# Harp_Motor_H2-module_v1_0.net
KiCad netlist of a schematic drawn in EAGLE
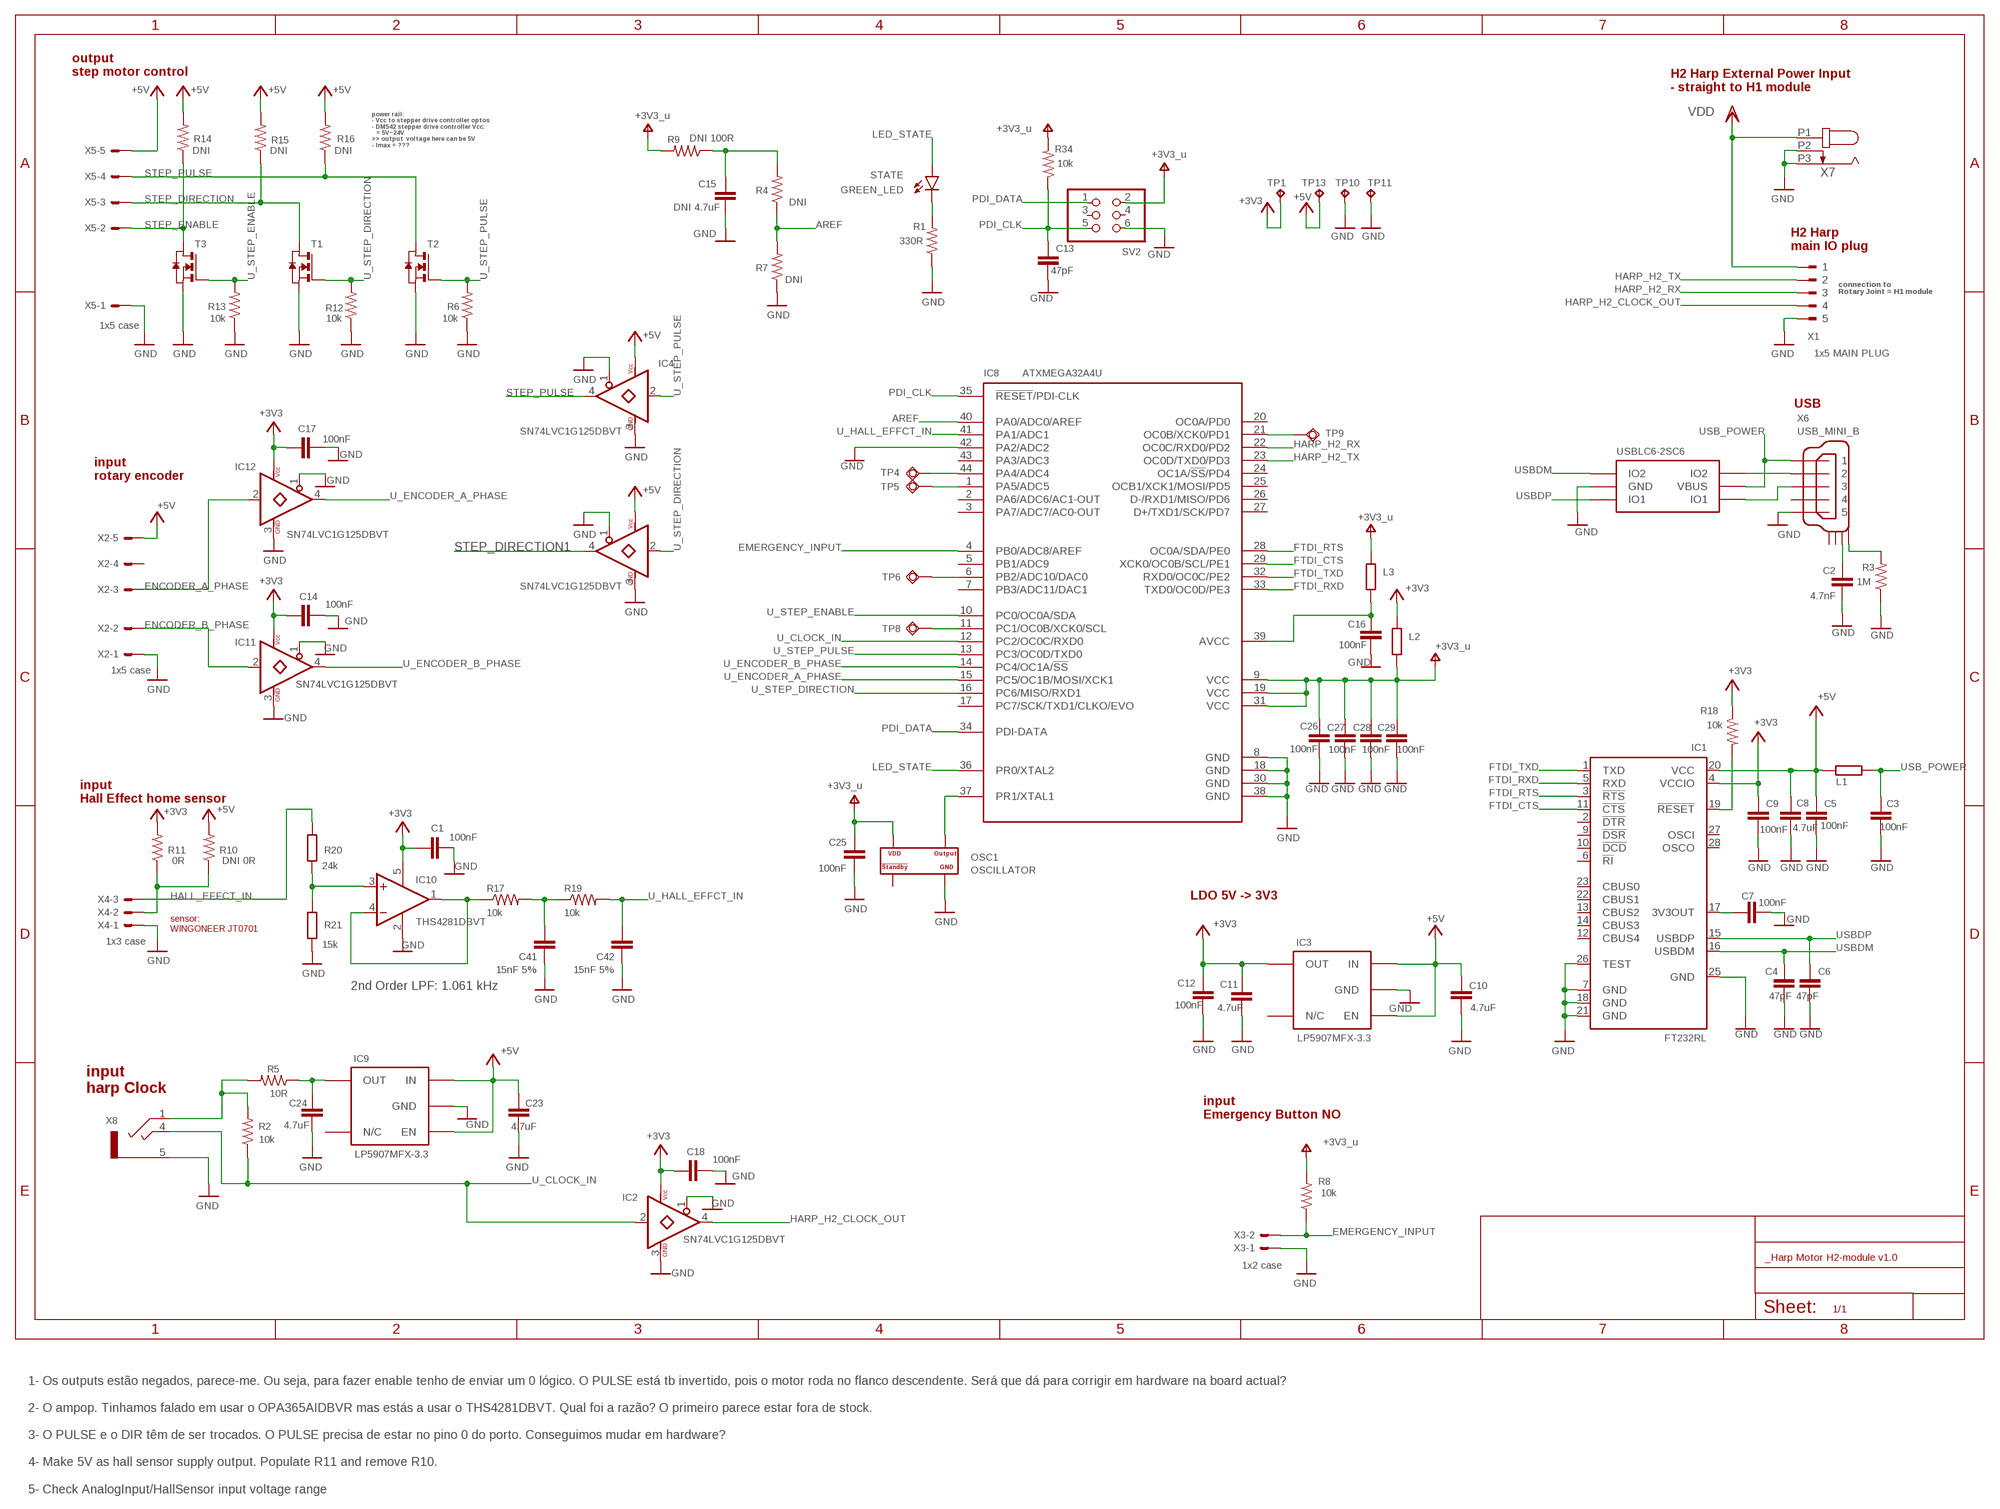
[diagram p0: schematic, sheet 1]

(export (version "E")
  (design (tool "Eeschema 10.0.6"))
  (components
    (comp (ref "C1")
      (value "100nF")
      (footprint "eagle-import:C0402K")
      (fields (field (name "MPN") "C1005X7R1H104K050BB"))
      (libsource (lib "eagle-import") (part "C-EUC0402K"))
    )
    (comp (ref "C2")
      (value "4.7nF")
      (footprint "eagle-import:C0402K")
      (fields (field (name "MPN") "CC0402KRX7R8BB472"))
      (libsource (lib "eagle-import") (part "C-EUC0402K"))
    )
    (comp (ref "C3")
      (value "100nF")
      (footprint "eagle-import:C0402K")
      (fields (field (name "MPN") "C1005X7R1H104K050BB"))
      (libsource (lib "eagle-import") (part "C-EUC0402K"))
    )
    (comp (ref "C4")
      (value "47pF")
      (footprint "eagle-import:C0402K")
      (fields (field (name "MPN") "04025A470JAT2A"))
      (libsource (lib "eagle-import") (part "C-EUC0402K"))
    )
    (comp (ref "C5")
      (value "100nF")
      (footprint "eagle-import:C0402K")
      (fields (field (name "MPN") "C1005X7R1H104K050BB"))
      (libsource (lib "eagle-import") (part "C-EUC0402K"))
    )
    (comp (ref "C6")
      (value "47pF")
      (footprint "eagle-import:C0402K")
      (fields (field (name "MPN") "04025A470JAT2A"))
      (libsource (lib "eagle-import") (part "C-EUC0402K"))
    )
    (comp (ref "C7")
      (value "100nF")
      (footprint "eagle-import:C0402K")
      (fields (field (name "MPN") "C1005X7R1H104K050BB"))
      (libsource (lib "eagle-import") (part "C-EUC0402K"))
    )
    (comp (ref "C8")
      (value "4.7uF")
      (footprint "eagle-import:C0603K")
      (fields (field (name "MPN") "C1608X6S1C475K080AC"))
      (libsource (lib "eagle-import") (part "C-EUC0603K"))
    )
    (comp (ref "C9")
      (value "100nF")
      (footprint "eagle-import:C0402K")
      (fields (field (name "MPN") "C1005X7R1H104K050BB"))
      (libsource (lib "eagle-import") (part "C-EUC0402K"))
    )
    (comp (ref "C10")
      (value "4.7uF")
      (footprint "eagle-import:C0603K")
      (fields (field (name "MPN") "C1608X6S1C475K080AC"))
      (libsource (lib "eagle-import") (part "C-EUC0603K"))
    )
    (comp (ref "C11")
      (value "4.7uF")
      (footprint "eagle-import:C0603K")
      (fields (field (name "MPN") "C1608X6S1C475K080AC"))
      (libsource (lib "eagle-import") (part "C-EUC0603K"))
    )
    (comp (ref "C12")
      (value "100nF")
      (footprint "eagle-import:C0402K")
      (fields (field (name "MPN") "C1005X7R1H104K050BB"))
      (libsource (lib "eagle-import") (part "C-EUC0402K"))
    )
    (comp (ref "C13")
      (value "47pF")
      (footprint "eagle-import:C0402K")
      (fields (field (name "MPN") "04025A470JAT2A"))
      (libsource (lib "eagle-import") (part "C-EUC0402K"))
    )
    (comp (ref "C14")
      (value "100nF")
      (footprint "eagle-import:C0402K")
      (fields (field (name "MPN") "C1005X7R1H104K050BB"))
      (libsource (lib "eagle-import") (part "C-EUC0402K"))
    )
    (comp (ref "C15")
      (value "DNI 4.7uF")
      (footprint "eagle-import:C0603K")
      (fields (field (name "MPN") "C1608X6S1C475K080AC"))
      (libsource (lib "eagle-import") (part "C-EUC0603K"))
    )
    (comp (ref "C16")
      (value "100nF")
      (footprint "eagle-import:C0402K")
      (fields (field (name "MPN") "C1005X7R1H104K050BB"))
      (libsource (lib "eagle-import") (part "C-EUC0402K"))
    )
    (comp (ref "C17")
      (value "100nF")
      (footprint "eagle-import:C0402K")
      (fields (field (name "MPN") "C1005X7R1H104K050BB"))
      (libsource (lib "eagle-import") (part "C-EUC0402K"))
    )
    (comp (ref "C18")
      (value "100nF")
      (footprint "eagle-import:C0402K")
      (fields (field (name "MPN") "C1005X7R1H104K050BB"))
      (libsource (lib "eagle-import") (part "C-EUC0402K"))
    )
    (comp (ref "C23")
      (value "4.7uF")
      (footprint "eagle-import:C0603K")
      (fields (field (name "MPN") "C1608X6S1C475K080AC"))
      (libsource (lib "eagle-import") (part "C-EUC0603K"))
    )
    (comp (ref "C24")
      (value "4.7uF")
      (footprint "eagle-import:C0603K")
      (fields (field (name "MPN") "C1608X6S1C475K080AC"))
      (libsource (lib "eagle-import") (part "C-EUC0603K"))
    )
    (comp (ref "C25")
      (value "100nF")
      (footprint "eagle-import:C0402K")
      (fields (field (name "MPN") "C1005X7R1H104K050BB"))
      (libsource (lib "eagle-import") (part "C-EUC0402K"))
    )
    (comp (ref "C26")
      (value "100nF")
      (footprint "eagle-import:C0402K")
      (fields (field (name "MPN") "C1005X7R1H104K050BB"))
      (libsource (lib "eagle-import") (part "C-EUC0402K"))
    )
    (comp (ref "C27")
      (value "100nF")
      (footprint "eagle-import:C0402K")
      (fields (field (name "MPN") "C1005X7R1H104K050BB"))
      (libsource (lib "eagle-import") (part "C-EUC0402K"))
    )
    (comp (ref "C28")
      (value "100nF")
      (footprint "eagle-import:C0402K")
      (fields (field (name "MPN") "C1005X7R1H104K050BB"))
      (libsource (lib "eagle-import") (part "C-EUC0402K"))
    )
    (comp (ref "C29")
      (value "100nF")
      (footprint "eagle-import:C0402K")
      (fields (field (name "MPN") "C1005X7R1H104K050BB"))
      (libsource (lib "eagle-import") (part "C-EUC0402K"))
    )
    (comp (ref "C41")
      (value "15nF 5%")
      (footprint "eagle-import:C0402K")
      (fields (field (name "MPN") "CGA2B3X7R1V153K050BB"))
      (libsource (lib "eagle-import") (part "C-EUC0402K"))
    )
    (comp (ref "C42")
      (value "15nF 5%")
      (footprint "eagle-import:C0402K")
      (fields (field (name "MPN") "CGA2B3X7R1V153K050BB"))
      (libsource (lib "eagle-import") (part "C-EUC0402K"))
    )
    (comp (ref "IC1")
      (value "FT232RL")
      (footprint "eagle-import:SSOP28")
      (libsource (lib "eagle-import") (part "FT232RL"))
    )
    (comp (ref "IC2")
      (value "SN74LVC1G125DBVT")
      (footprint "eagle-import:SOT23-5")
      (libsource (lib "eagle-import") (part "741G125DBVLVC"))
    )
    (comp (ref "IC3")
      (value "LP5907MFX-3.3")
      (footprint "eagle-import:TSOT23-5")
      (fields (field (name "MPN") "LP5907MFX-3.3/NOPB"))
      (libsource (lib "eagle-import") (part "TLV700XX"))
    )
    (comp (ref "IC4")
      (value "SN74LVC1G125DBVT")
      (footprint "eagle-import:SOT23-5")
      (libsource (lib "eagle-import") (part "741G125DBVLVC"))
    )
    (comp (ref "IC5")
      (value "SN74LVC1G125DBVT")
      (footprint "eagle-import:SOT23-5")
      (libsource (lib "eagle-import") (part "741G125DBVLVC"))
    )
    (comp (ref "IC7")
      (value "USBLC6-2SC6")
      (footprint "eagle-import:SOT23-6L")
      (libsource (lib "eagle-import") (part "USBLC6-2SC6"))
    )
    (comp (ref "IC8")
      (value "ATXMEGA32A4U")
      (footprint "eagle-import:TQFP44")
      (fields (field (name "MPN") "ATXMEGA32A4U-AUR"))
      (libsource (lib "eagle-import") (part "XMEGA-A4_AT-XMEGA-XXA4-AUTQFP44"))
    )
    (comp (ref "IC9")
      (value "LP5907MFX-3.3")
      (footprint "eagle-import:TSOT23-5")
      (fields (field (name "MPN") "LP5907MFX-3.3/NOPB"))
      (libsource (lib "eagle-import") (part "TLV700XX"))
    )
    (comp (ref "IC10")
      (value "THS4281DBVT")
      (footprint "eagle-import:SOT23-5")
      (libsource (lib "eagle-import") (part "OPA365"))
    )
    (comp (ref "IC11")
      (value "SN74LVC1G125DBVT")
      (footprint "eagle-import:SOT23-5")
      (libsource (lib "eagle-import") (part "741G125DBVLVC"))
    )
    (comp (ref "IC12")
      (value "SN74LVC1G125DBVT")
      (footprint "eagle-import:SOT23-5")
      (libsource (lib "eagle-import") (part "741G125DBVLVC"))
    )
    (comp (ref "L1")
      (value "40R@100MHz")
      (footprint "eagle-import:R0805")
      (fields (field (name "MPN") "MI0805K400R-10"))
      (libsource (lib "eagle-import") (part "R-EU_R0805"))
    )
    (comp (ref "L2")
      (value "40R@100MHz")
      (footprint "eagle-import:R0805")
      (fields (field (name "MPN") "MI0805K400R-10"))
      (libsource (lib "eagle-import") (part "R-EU_R0805"))
    )
    (comp (ref "L3")
      (value "40R@100MHz")
      (footprint "eagle-import:R0805")
      (fields (field (name "MPN") "MI0805K400R-10"))
      (libsource (lib "eagle-import") (part "R-EU_R0805"))
    )
    (comp (ref "OSC1")
      (value "OSCILLATOR")
      (footprint "eagle-import:OSCILLATOR_3.2X2.5")
      (fields (field (name "MPN") "DSC1001CI5-032.0000"))
      (libsource (lib "eagle-import") (part "OSCILLATOR"))
    )
    (comp (ref "R1")
      (value "330R")
      (footprint "eagle-import:R0402")
      (fields (field (name "MPN") "RC0402FR-07330RL"))
      (libsource (lib "eagle-import") (part "R-US_R0402"))
    )
    (comp (ref "R2")
      (value "10k")
      (footprint "eagle-import:R0402")
      (fields (field (name "MPN") "CRCW040210K0FKED"))
      (libsource (lib "eagle-import") (part "R-US_R0402"))
    )
    (comp (ref "R3")
      (value "1M")
      (footprint "eagle-import:R0402")
      (fields (field (name "MPN") "CRCW04021M00FKED"))
      (libsource (lib "eagle-import") (part "R-US_R0402"))
    )
    (comp (ref "R4")
      (value "DNI")
      (footprint "eagle-import:R0402")
      (libsource (lib "eagle-import") (part "R-US_R0402"))
    )
    (comp (ref "R5")
      (value "10R")
      (footprint "eagle-import:R0402")
      (fields (field (name "MPN") "ERJ-PA2J100X "))
      (libsource (lib "eagle-import") (part "R-US_R0402"))
    )
    (comp (ref "R6")
      (value "10k")
      (footprint "eagle-import:R0402")
      (fields (field (name "MPN") "CRCW040210K0FKED"))
      (libsource (lib "eagle-import") (part "R-US_R0402"))
    )
    (comp (ref "R7")
      (value "DNI")
      (footprint "eagle-import:R0402")
      (libsource (lib "eagle-import") (part "R-US_R0402"))
    )
    (comp (ref "R8")
      (value "10k")
      (footprint "eagle-import:R0402")
      (fields (field (name "MPN") "CRCW040210K0FKED"))
      (libsource (lib "eagle-import") (part "R-US_R0402"))
    )
    (comp (ref "R9")
      (value "DNI 100R")
      (footprint "eagle-import:R0402")
      (fields (field (name "MPN") "ERJ-2RKF1000X "))
      (libsource (lib "eagle-import") (part "R-US_R0402"))
    )
    (comp (ref "R10")
      (value "DNI 0R")
      (footprint "eagle-import:R0402")
      (fields (field (name "MPN") "RC0402JR-070RL"))
      (libsource (lib "eagle-import") (part "R-US_R0402"))
    )
    (comp (ref "R11")
      (value "0R")
      (footprint "eagle-import:R0402")
      (fields (field (name "MPN") "RC0402JR-070RL"))
      (libsource (lib "eagle-import") (part "R-US_R0402"))
    )
    (comp (ref "R12")
      (value "10k")
      (footprint "eagle-import:R0402")
      (fields (field (name "MPN") "CRCW040210K0FKED"))
      (libsource (lib "eagle-import") (part "R-US_R0402"))
    )
    (comp (ref "R13")
      (value "10k")
      (footprint "eagle-import:R0402")
      (fields (field (name "MPN") "CRCW040210K0FKED"))
      (libsource (lib "eagle-import") (part "R-US_R0402"))
    )
    (comp (ref "R14")
      (value "DNI")
      (footprint "eagle-import:R0402")
      (libsource (lib "eagle-import") (part "R-US_R0402"))
    )
    (comp (ref "R15")
      (value "DNI")
      (footprint "eagle-import:R0402")
      (libsource (lib "eagle-import") (part "R-US_R0402"))
    )
    (comp (ref "R16")
      (value "DNI")
      (footprint "eagle-import:R0402")
      (libsource (lib "eagle-import") (part "R-US_R0402"))
    )
    (comp (ref "R17")
      (value "10k")
      (footprint "eagle-import:R0402")
      (fields (field (name "MPN") "CRCW040210K0FKED"))
      (libsource (lib "eagle-import") (part "R-US_R0402"))
    )
    (comp (ref "R18")
      (value "10k")
      (footprint "eagle-import:R0402")
      (fields (field (name "MPN") "CRCW040210K0FKED"))
      (libsource (lib "eagle-import") (part "R-US_R0402"))
    )
    (comp (ref "R19")
      (value "10k")
      (footprint "eagle-import:R0402")
      (fields (field (name "MPN") "CRCW040210K0FKED"))
      (libsource (lib "eagle-import") (part "R-US_R0402"))
    )
    (comp (ref "R20")
      (value "24k")
      (footprint "eagle-import:R0402")
      (fields (field (name "MPN") "ERJ-2RKF2402X"))
      (libsource (lib "eagle-import") (part "R-EU_R0402"))
    )
    (comp (ref "R21")
      (value "15k")
      (footprint "eagle-import:R0402")
      (fields (field (name "MPN") "ERJ-2RKF1502X"))
      (libsource (lib "eagle-import") (part "R-EU_R0402"))
    )
    (comp (ref "R34")
      (value "10k")
      (footprint "eagle-import:R0402")
      (fields (field (name "MPN") "CRCW040210K0FKED"))
      (libsource (lib "eagle-import") (part "R-US_R0402"))
    )
    (comp (ref "STATE")
      (value "GREEN_LED")
      (footprint "eagle-import:CHIP-LED0603")
      (fields (field (name "MPN") "LTST-C191KGKT"))
      (libsource (lib "eagle-import") (part "LEDCHIP-LED0603"))
    )
    (comp (ref "SV2")
      (value "PINHD-2X3")
      (footprint "eagle-import:2X03")
      (fields (field (name "MPN") "609-3210-ND"))
      (libsource (lib "eagle-import") (part "PINHD-2X3"))
    )
    (comp (ref "T1")
      (value "DMG1012UW")
      (footprint "eagle-import:SOT323")
      (fields (field (name "MPN") "DMG1012UW-7"))
      (libsource (lib "eagle-import") (part "DMG1012UW-7"))
    )
    (comp (ref "T2")
      (value "DMG1012UW")
      (footprint "eagle-import:SOT323")
      (fields (field (name "MPN") "DMG1012UW-7"))
      (libsource (lib "eagle-import") (part "DMG1012UW-7"))
    )
    (comp (ref "T3")
      (value "DMG1012UW")
      (footprint "eagle-import:SOT323")
      (fields (field (name "MPN") "DMG1012UW-7"))
      (libsource (lib "eagle-import") (part "DMG1012UW-7"))
    )
    (comp (ref "TP1")
      (value "NO_COMPONENT")
      (footprint "eagle-import:B1,27")
      (libsource (lib "eagle-import") (part "TPB1,27"))
    )
    (comp (ref "TP4")
      (value "NO_COMPONENT")
      (footprint "eagle-import:TP11R")
      (libsource (lib "eagle-import") (part "TPSQTP11R"))
    )
    (comp (ref "TP5")
      (value "NO_COMPONENT")
      (footprint "eagle-import:TP11R")
      (libsource (lib "eagle-import") (part "TPSQTP11R"))
    )
    (comp (ref "TP6")
      (value "NO_COMPONENT")
      (footprint "eagle-import:TP11R")
      (libsource (lib "eagle-import") (part "TPSQTP11R"))
    )
    (comp (ref "TP8")
      (value "NO_COMPONENT")
      (footprint "eagle-import:TP11R")
      (libsource (lib "eagle-import") (part "TPSQTP11R"))
    )
    (comp (ref "TP9")
      (value "NO_COMPONENT")
      (footprint "eagle-import:TP11R")
      (libsource (lib "eagle-import") (part "TPSQTP11R"))
    )
    (comp (ref "TP10")
      (value "NO_COMPONENT")
      (footprint "eagle-import:B1,27")
      (libsource (lib "eagle-import") (part "TPB1,27"))
    )
    (comp (ref "TP11")
      (value "NO_COMPONENT")
      (footprint "eagle-import:B1,27")
      (libsource (lib "eagle-import") (part "TPB1,27"))
    )
    (comp (ref "TP13")
      (value "NO_COMPONENT")
      (footprint "eagle-import:B1,27")
      (libsource (lib "eagle-import") (part "TPB1,27"))
    )
    (comp (ref "X1")
      (value "1x5 MAIN PLUG")
      (footprint "eagle-import:90G-5")
      (fields (field (name "MPN") "20.155MH/5-E"))
      (libsource (lib "eagle-import") (part "90G-5"))
    )
    (comp (ref "X2")
      (value "1x5 case")
      (footprint "eagle-import:22-23-2051")
      (fields (field (name "MPN") "282834-5") (field (name "OEPS") "OEPS070041"))
      (libsource (lib "eagle-import") (part "22-23-2051"))
    )
    (comp (ref "X3")
      (value "1x2 case")
      (footprint "eagle-import:22-23-2021")
      (fields (field (name "MPN") "282834-2"))
      (libsource (lib "eagle-import") (part "22-23-2021"))
    )
    (comp (ref "X4")
      (value "1x3 case")
      (footprint "eagle-import:22-23-2031")
      (fields (field (name "MPN") "282834-3") (field (name "OEPS") "OEPS070035"))
      (libsource (lib "eagle-import") (part "22-23-2031"))
    )
    (comp (ref "X5")
      (value "1x5 case")
      (footprint "eagle-import:22-23-2051")
      (fields (field (name "MPN") "282834-5") (field (name "OEPS") "OEPS070041"))
      (libsource (lib "eagle-import") (part "22-23-2051"))
    )
    (comp (ref "X6")
      (value "USB_MINI_B")
      (footprint "eagle-import:240-0002-1")
      (fields (field (name "MPN") "UX60-MB-5S8"))
      (libsource (lib "eagle-import") (part "USB_MINI_B"))
    )
    (comp (ref "X7")
      (value "DC_JACK2.1MM")
      (footprint "eagle-import:DC_POWER_INPUT_2.1MM")
      (fields (field (name "MPN") "163-179PH-EX"))
      (libsource (lib "eagle-import") (part "DC_JACK2.1MM"))
    )
    (comp (ref "X8")
      (value "CLCK_JACK")
      (footprint "eagle-import:35RASMT2BHNTRX")
      (fields (field (name "MPN") "35RASMT2BHNTRX"))
      (libsource (lib "eagle-import") (part "STEREO_JACK"))
    )
  )
  (nets
    (net (code "1") (name "+3V3") (class "Default")
      (node (ref "C1") (pin "1") (pinfunction "1_1") (pintype "passive"))
      (node (ref "C11") (pin "1") (pinfunction "1_1") (pintype "passive"))
      (node (ref "C12") (pin "1") (pinfunction "1_1") (pintype "passive"))
      (node (ref "C14") (pin "1") (pinfunction "1_1") (pintype "passive"))
      (node (ref "C17") (pin "1") (pinfunction "1_1") (pintype "passive"))
      (node (ref "C18") (pin "1") (pinfunction "1_1") (pintype "passive"))
      (node (ref "C9") (pin "1") (pinfunction "1_1") (pintype "passive"))
      (node (ref "IC1") (pin "4") (pinfunction "VCCIO_4") (pintype "power_in"))
      (node (ref "IC10") (pin "5") (pinfunction "V+_5") (pintype "power_in"))
      (node (ref "IC11") (pin "5") (pinfunction "VCC_5") (pintype "passive"))
      (node (ref "IC12") (pin "5") (pinfunction "VCC_5") (pintype "passive"))
      (node (ref "IC2") (pin "5") (pinfunction "VCC_5") (pintype "passive"))
      (node (ref "IC3") (pin "5") (pinfunction "OUT_5") (pintype "bidirectional"))
      (node (ref "L2") (pin "2") (pinfunction "2_2") (pintype "passive"))
      (node (ref "R11") (pin "2") (pinfunction "2_2") (pintype "passive"))
      (node (ref "R18") (pin "1") (pinfunction "1_1") (pintype "passive"))
      (node (ref "TP1") (pin "TP") (pinfunction "TP_TP") (pintype "input"))
    )
    (net (code "2") (name "+3V3_u") (class "Default")
      (node (ref "C25") (pin "1") (pinfunction "1_1") (pintype "passive"))
      (node (ref "C26") (pin "1") (pinfunction "1_1") (pintype "passive"))
      (node (ref "C27") (pin "1") (pinfunction "1_1") (pintype "passive"))
      (node (ref "C28") (pin "1") (pinfunction "1_1") (pintype "passive"))
      (node (ref "C29") (pin "1") (pinfunction "1_1") (pintype "passive"))
      (node (ref "IC8") (pin "19") (pinfunction "VCC_19") (pintype "power_in"))
      (node (ref "IC8") (pin "31") (pinfunction "VCC_31") (pintype "power_in"))
      (node (ref "IC8") (pin "9") (pinfunction "VCC_9") (pintype "power_in"))
      (node (ref "L2") (pin "1") (pinfunction "1_1") (pintype "passive"))
      (node (ref "L3") (pin "2") (pinfunction "2_2") (pintype "passive"))
      (node (ref "OSC1") (pin "P$4") (pinfunction "VDD_P$4") (pintype "passive"))
      (node (ref "R34") (pin "2") (pinfunction "2_2") (pintype "passive"))
      (node (ref "R8") (pin "2") (pinfunction "2_2") (pintype "passive"))
      (node (ref "R9") (pin "2") (pinfunction "2_2") (pintype "passive"))
      (node (ref "SV2") (pin "2") (pinfunction "2_2") (pintype "passive"))
    )
    (net (code "3") (name "+5V") (class "Default")
      (node (ref "C10") (pin "1") (pinfunction "1_1") (pintype "passive"))
      (node (ref "C23") (pin "1") (pinfunction "1_1") (pintype "passive"))
      (node (ref "C5") (pin "1") (pinfunction "1_1") (pintype "passive"))
      (node (ref "C8") (pin "1") (pinfunction "1_1") (pintype "passive"))
      (node (ref "IC1") (pin "20") (pinfunction "VCC_20") (pintype "power_in"))
      (node (ref "IC3") (pin "1") (pinfunction "IN_1") (pintype "bidirectional"))
      (node (ref "IC3") (pin "3") (pinfunction "EN_3") (pintype "bidirectional"))
      (node (ref "IC4") (pin "5") (pinfunction "VCC_5") (pintype "passive"))
      (node (ref "IC5") (pin "5") (pinfunction "VCC_5") (pintype "passive"))
      (node (ref "IC9") (pin "1") (pinfunction "IN_1") (pintype "bidirectional"))
      (node (ref "IC9") (pin "3") (pinfunction "EN_3") (pintype "bidirectional"))
      (node (ref "L1") (pin "1") (pinfunction "1_1") (pintype "passive"))
      (node (ref "R10") (pin "2") (pinfunction "2_2") (pintype "passive"))
      (node (ref "R14") (pin "2") (pinfunction "2_2") (pintype "passive"))
      (node (ref "R15") (pin "2") (pinfunction "2_2") (pintype "passive"))
      (node (ref "R16") (pin "2") (pinfunction "2_2") (pintype "passive"))
      (node (ref "TP13") (pin "TP") (pinfunction "TP_TP") (pintype "input"))
      (node (ref "X2") (pin "5") (pinfunction "S_5") (pintype "passive"))
      (node (ref "X5") (pin "5") (pinfunction "S_5") (pintype "passive"))
    )
    (net (code "4") (name "/AREF") (class "Default")
      (node (ref "IC8") (pin "40") (pinfunction "PA0/ADC0/AREF_40") (pintype "bidirectional"))
      (node (ref "R4") (pin "1") (pinfunction "1_1") (pintype "passive"))
      (node (ref "R7") (pin "2") (pinfunction "2_2") (pintype "passive"))
    )
    (net (code "5") (name "/EMERGENCY_INPUT") (class "Default")
      (node (ref "IC8") (pin "4") (pinfunction "PB0/ADC8/AREF_4") (pintype "bidirectional"))
      (node (ref "R8") (pin "1") (pinfunction "1_1") (pintype "passive"))
      (node (ref "X3") (pin "2") (pinfunction "S_2") (pintype "passive"))
    )
    (net (code "6") (name "/ENCODER_A_PHASE") (class "Default")
      (node (ref "IC12") (pin "2") (pinfunction "I_2") (pintype "input"))
      (node (ref "X2") (pin "3") (pinfunction "S_3") (pintype "passive"))
    )
    (net (code "7") (name "/ENCODER_B_PHASE") (class "Default")
      (node (ref "IC11") (pin "2") (pinfunction "I_2") (pintype "input"))
      (node (ref "X2") (pin "2") (pinfunction "S_2") (pintype "passive"))
    )
    (net (code "8") (name "/FTDI_CTS") (class "Default")
      (node (ref "IC1") (pin "11") (pinfunction "~{CTS}_11") (pintype "input"))
      (node (ref "IC8") (pin "29") (pinfunction "XCK0/OC0B/SCL/PE1_29") (pintype "bidirectional"))
    )
    (net (code "9") (name "/FTDI_RTS") (class "Default")
      (node (ref "IC1") (pin "3") (pinfunction "~{RTS}_3") (pintype "output"))
      (node (ref "IC8") (pin "28") (pinfunction "OC0A/SDA/PE0_28") (pintype "bidirectional"))
    )
    (net (code "10") (name "/FTDI_RXD") (class "Default")
      (node (ref "IC1") (pin "5") (pinfunction "RXD_5") (pintype "input"))
      (node (ref "IC8") (pin "33") (pinfunction "TXD0/OC0D/PE3_33") (pintype "bidirectional"))
    )
    (net (code "11") (name "/FTDI_TXD") (class "Default")
      (node (ref "IC1") (pin "1") (pinfunction "TXD_1") (pintype "output"))
      (node (ref "IC8") (pin "32") (pinfunction "RXD0/OC0C/PE2_32") (pintype "bidirectional"))
    )
    (net (code "12") (name "/HALL_EFFCT_IN") (class "Default")
      (node (ref "R20") (pin "2") (pinfunction "2_2") (pintype "passive"))
      (node (ref "X4") (pin "3") (pinfunction "S_3") (pintype "passive"))
    )
    (net (code "13") (name "/HARP_H2_CLOCK_OUT") (class "Default")
      (node (ref "IC2") (pin "4") (pinfunction "O_4") (pintype "tri_state"))
      (node (ref "X1") (pin "4") (pinfunction "4_4") (pintype "passive"))
    )
    (net (code "14") (name "/HARP_H2_RX") (class "Default")
      (node (ref "IC8") (pin "22") (pinfunction "OC0C/RXD0/PD2_22") (pintype "bidirectional"))
      (node (ref "X1") (pin "3") (pinfunction "3_3") (pintype "passive"))
    )
    (net (code "15") (name "/HARP_H2_TX") (class "Default")
      (node (ref "IC8") (pin "23") (pinfunction "OC0D/TXD0/PD3_23") (pintype "bidirectional"))
      (node (ref "X1") (pin "2") (pinfunction "2_2") (pintype "passive"))
    )
    (net (code "16") (name "/LED_STATE") (class "Default")
      (node (ref "IC8") (pin "36") (pinfunction "PR0/XTAL2_36") (pintype "bidirectional"))
      (node (ref "STATE") (pin "A") (pinfunction "A_A") (pintype "passive"))
    )
    (net (code "17") (name "/PDI_CLK") (class "Default")
      (node (ref "C13") (pin "1") (pinfunction "1_1") (pintype "passive"))
      (node (ref "IC8") (pin "35") (pinfunction "~{RESET}/PDI-CLK_35") (pintype "input"))
      (node (ref "R34") (pin "1") (pinfunction "1_1") (pintype "passive"))
      (node (ref "SV2") (pin "5") (pinfunction "5_5") (pintype "passive"))
    )
    (net (code "18") (name "/PDI_DATA") (class "Default")
      (node (ref "IC8") (pin "34") (pinfunction "PDI-DATA_34") (pintype "bidirectional"))
      (node (ref "SV2") (pin "1") (pinfunction "1_1") (pintype "passive"))
    )
    (net (code "19") (name "/STEP_DIRECTION") (class "Default")
      (node (ref "R15") (pin "1") (pinfunction "1_1") (pintype "passive"))
      (node (ref "T1") (pin "3") (pinfunction "D_3") (pintype "passive"))
      (node (ref "X5") (pin "3") (pinfunction "S_3") (pintype "passive"))
    )
    (net (code "20") (name "/STEP_DIRECTION1") (class "Default")
      (node (ref "IC5") (pin "4") (pinfunction "O_4") (pintype "tri_state"))
    )
    (net (code "21") (name "/STEP_ENABLE") (class "Default")
      (node (ref "R14") (pin "1") (pinfunction "1_1") (pintype "passive"))
      (node (ref "T3") (pin "3") (pinfunction "D_3") (pintype "passive"))
      (node (ref "X5") (pin "2") (pinfunction "S_2") (pintype "passive"))
    )
    (net (code "22") (name "/STEP_PULSE") (class "Default")
      (node (ref "IC4") (pin "4") (pinfunction "O_4") (pintype "tri_state"))
      (node (ref "R16") (pin "1") (pinfunction "1_1") (pintype "passive"))
      (node (ref "T2") (pin "3") (pinfunction "D_3") (pintype "passive"))
      (node (ref "X5") (pin "4") (pinfunction "S_4") (pintype "passive"))
    )
    (net (code "23") (name "/USBDM") (class "Default")
      (node (ref "C4") (pin "1") (pinfunction "1_1") (pintype "passive"))
      (node (ref "IC1") (pin "16") (pinfunction "USBDM_16") (pintype "bidirectional"))
      (node (ref "IC7") (pin "P$3") (pinfunction "IO2_P$3") (pintype "bidirectional"))
    )
    (net (code "24") (name "/USBDP") (class "Default")
      (node (ref "C6") (pin "1") (pinfunction "1_1") (pintype "passive"))
      (node (ref "IC1") (pin "15") (pinfunction "USBDP_15") (pintype "bidirectional"))
      (node (ref "IC7") (pin "P$1") (pinfunction "IO1_P$1") (pintype "bidirectional"))
    )
    (net (code "25") (name "/USB_POWER") (class "Default")
      (node (ref "C3") (pin "1") (pinfunction "1_1") (pintype "passive"))
      (node (ref "IC7") (pin "P$5") (pinfunction "VBUS_P$5") (pintype "bidirectional"))
      (node (ref "L1") (pin "2") (pinfunction "2_2") (pintype "passive"))
      (node (ref "X6") (pin "P$1") (pinfunction "1_P$1") (pintype "bidirectional"))
    )
    (net (code "26") (name "/U_CLOCK_IN") (class "Default")
      (node (ref "IC2") (pin "2") (pinfunction "I_2") (pintype "input"))
      (node (ref "IC8") (pin "12") (pinfunction "PC2/OC0C/RXD0_12") (pintype "bidirectional"))
      (node (ref "R2") (pin "1") (pinfunction "1_1") (pintype "passive"))
      (node (ref "X8") (pin "4") (pinfunction "4_4") (pintype "passive"))
    )
    (net (code "27") (name "/U_ENCODER_A_PHASE") (class "Default")
      (node (ref "IC12") (pin "4") (pinfunction "O_4") (pintype "tri_state"))
      (node (ref "IC8") (pin "15") (pinfunction "PC5/OC1B/MOSI/XCK1_15") (pintype "bidirectional"))
    )
    (net (code "28") (name "/U_ENCODER_B_PHASE") (class "Default")
      (node (ref "IC11") (pin "4") (pinfunction "O_4") (pintype "tri_state"))
      (node (ref "IC8") (pin "14") (pinfunction "PC4/OC1A/~{SS}_14") (pintype "bidirectional"))
    )
    (net (code "29") (name "/U_HALL_EFFCT_IN") (class "Default")
      (node (ref "C42") (pin "2") (pinfunction "2_2") (pintype "passive"))
      (node (ref "IC8") (pin "41") (pinfunction "PA1/ADC1_41") (pintype "bidirectional"))
      (node (ref "R19") (pin "2") (pinfunction "2_2") (pintype "passive"))
    )
    (net (code "30") (name "/U_STEP_DIRECTION") (class "Default")
      (node (ref "IC5") (pin "2") (pinfunction "I_2") (pintype "input"))
      (node (ref "IC8") (pin "16") (pinfunction "PC6/MISO/RXD1_16") (pintype "bidirectional"))
      (node (ref "R12") (pin "2") (pinfunction "2_2") (pintype "passive"))
      (node (ref "T1") (pin "1") (pinfunction "G_1") (pintype "passive"))
    )
    (net (code "31") (name "/U_STEP_ENABLE") (class "Default")
      (node (ref "IC8") (pin "10") (pinfunction "PC0/OC0A/SDA_10") (pintype "bidirectional"))
      (node (ref "R13") (pin "2") (pinfunction "2_2") (pintype "passive"))
      (node (ref "T3") (pin "1") (pinfunction "G_1") (pintype "passive"))
    )
    (net (code "32") (name "/U_STEP_PULSE") (class "Default")
      (node (ref "IC4") (pin "2") (pinfunction "I_2") (pintype "input"))
      (node (ref "IC8") (pin "13") (pinfunction "PC3/OC0D/TXD0_13") (pintype "bidirectional"))
      (node (ref "R6") (pin "2") (pinfunction "2_2") (pintype "passive"))
      (node (ref "T2") (pin "1") (pinfunction "G_1") (pintype "passive"))
    )
    (net (code "33") (name "GND") (class "Default")
      (node (ref "C1") (pin "2") (pinfunction "2_2") (pintype "passive"))
      (node (ref "C10") (pin "2") (pinfunction "2_2") (pintype "passive"))
      (node (ref "C11") (pin "2") (pinfunction "2_2") (pintype "passive"))
      (node (ref "C12") (pin "2") (pinfunction "2_2") (pintype "passive"))
      (node (ref "C13") (pin "2") (pinfunction "2_2") (pintype "passive"))
      (node (ref "C14") (pin "2") (pinfunction "2_2") (pintype "passive"))
      (node (ref "C15") (pin "2") (pinfunction "2_2") (pintype "passive"))
      (node (ref "C16") (pin "2") (pinfunction "2_2") (pintype "passive"))
      (node (ref "C17") (pin "2") (pinfunction "2_2") (pintype "passive"))
      (node (ref "C18") (pin "2") (pinfunction "2_2") (pintype "passive"))
      (node (ref "C2") (pin "2") (pinfunction "2_2") (pintype "passive"))
      (node (ref "C23") (pin "2") (pinfunction "2_2") (pintype "passive"))
      (node (ref "C24") (pin "2") (pinfunction "2_2") (pintype "passive"))
      (node (ref "C25") (pin "2") (pinfunction "2_2") (pintype "passive"))
      (node (ref "C26") (pin "2") (pinfunction "2_2") (pintype "passive"))
      (node (ref "C27") (pin "2") (pinfunction "2_2") (pintype "passive"))
      (node (ref "C28") (pin "2") (pinfunction "2_2") (pintype "passive"))
      (node (ref "C29") (pin "2") (pinfunction "2_2") (pintype "passive"))
      (node (ref "C3") (pin "2") (pinfunction "2_2") (pintype "passive"))
      (node (ref "C4") (pin "2") (pinfunction "2_2") (pintype "passive"))
      (node (ref "C41") (pin "1") (pinfunction "1_1") (pintype "passive"))
      (node (ref "C42") (pin "1") (pinfunction "1_1") (pintype "passive"))
      (node (ref "C5") (pin "2") (pinfunction "2_2") (pintype "passive"))
      (node (ref "C6") (pin "2") (pinfunction "2_2") (pintype "passive"))
      (node (ref "C7") (pin "2") (pinfunction "2_2") (pintype "passive"))
      (node (ref "C8") (pin "2") (pinfunction "2_2") (pintype "passive"))
      (node (ref "C9") (pin "2") (pinfunction "2_2") (pintype "passive"))
      (node (ref "IC1") (pin "18") (pinfunction "GND_18") (pintype "power_in"))
      (node (ref "IC1") (pin "21") (pinfunction "GND_21") (pintype "power_in"))
      (node (ref "IC1") (pin "25") (pinfunction "GND_25") (pintype "power_in"))
      (node (ref "IC1") (pin "26") (pinfunction "TEST_26") (pintype "input"))
      (node (ref "IC1") (pin "7") (pinfunction "GND_7") (pintype "power_in"))
      (node (ref "IC10") (pin "2") (pinfunction "V-_2") (pintype "power_in"))
      (node (ref "IC11") (pin "1") (pinfunction "OE_1") (pintype "input"))
      (node (ref "IC11") (pin "3") (pinfunction "GND_3") (pintype "power_in"))
      (node (ref "IC12") (pin "1") (pinfunction "OE_1") (pintype "input"))
      (node (ref "IC12") (pin "3") (pinfunction "GND_3") (pintype "power_in"))
      (node (ref "IC2") (pin "1") (pinfunction "OE_1") (pintype "input"))
      (node (ref "IC2") (pin "3") (pinfunction "GND_3") (pintype "power_in"))
      (node (ref "IC3") (pin "2") (pinfunction "GND_2") (pintype "bidirectional"))
      (node (ref "IC4") (pin "1") (pinfunction "OE_1") (pintype "input"))
      (node (ref "IC4") (pin "3") (pinfunction "GND_3") (pintype "power_in"))
      (node (ref "IC5") (pin "1") (pinfunction "OE_1") (pintype "input"))
      (node (ref "IC5") (pin "3") (pinfunction "GND_3") (pintype "power_in"))
      (node (ref "IC7") (pin "P$2") (pinfunction "GND_P$2") (pintype "bidirectional"))
      (node (ref "IC8") (pin "18") (pinfunction "GND_18") (pintype "power_in"))
      (node (ref "IC8") (pin "30") (pinfunction "GND_30") (pintype "power_in"))
      (node (ref "IC8") (pin "38") (pinfunction "GND_38") (pintype "power_in"))
      (node (ref "IC8") (pin "42") (pinfunction "PA2/ADC2_42") (pintype "bidirectional"))
      (node (ref "IC8") (pin "8") (pinfunction "GND_8") (pintype "power_in"))
      (node (ref "IC9") (pin "2") (pinfunction "GND_2") (pintype "bidirectional"))
      (node (ref "OSC1") (pin "P$2") (pinfunction "GND_P$2") (pintype "passive"))
      (node (ref "R1") (pin "1") (pinfunction "1_1") (pintype "passive"))
      (node (ref "R12") (pin "1") (pinfunction "1_1") (pintype "passive"))
      (node (ref "R13") (pin "1") (pinfunction "1_1") (pintype "passive"))
      (node (ref "R21") (pin "1") (pinfunction "1_1") (pintype "passive"))
      (node (ref "R3") (pin "1") (pinfunction "1_1") (pintype "passive"))
      (node (ref "R6") (pin "1") (pinfunction "1_1") (pintype "passive"))
      (node (ref "R7") (pin "1") (pinfunction "1_1") (pintype "passive"))
      (node (ref "SV2") (pin "6") (pinfunction "6_6") (pintype "passive"))
      (node (ref "T1") (pin "2") (pinfunction "S_2") (pintype "passive"))
      (node (ref "T2") (pin "2") (pinfunction "S_2") (pintype "passive"))
      (node (ref "T3") (pin "2") (pinfunction "S_2") (pintype "passive"))
      (node (ref "TP10") (pin "TP") (pinfunction "TP_TP") (pintype "input"))
      (node (ref "TP11") (pin "TP") (pinfunction "TP_TP") (pintype "input"))
      (node (ref "X1") (pin "5") (pinfunction "5_5") (pintype "passive"))
      (node (ref "X2") (pin "1") (pinfunction "S_1") (pintype "passive"))
      (node (ref "X3") (pin "1") (pinfunction "S_1") (pintype "passive"))
      (node (ref "X4") (pin "1") (pinfunction "S_1") (pintype "passive"))
      (node (ref "X5") (pin "1") (pinfunction "S_1") (pintype "passive"))
      (node (ref "X6") (pin "P$5") (pinfunction "5_P$5") (pintype "bidirectional"))
      (node (ref "X7") (pin "P2") (pinfunction "2_P2") (pintype "passive"))
      (node (ref "X7") (pin "P3") (pinfunction "3_P3") (pintype "passive"))
      (node (ref "X8") (pin "5") (pinfunction "5_5") (pintype "passive"))
    )
    (net (code "34") (name "Net-(C15-Pad1)") (class "Default")
      (node (ref "C15") (pin "1") (pinfunction "1_1") (pintype "passive"))
      (node (ref "R4") (pin "2") (pinfunction "2_2") (pintype "passive"))
      (node (ref "R9") (pin "1") (pinfunction "1_1") (pintype "passive"))
    )
    (net (code "35") (name "Net-(C41-Pad2)") (class "Default")
      (node (ref "C41") (pin "2") (pinfunction "2_2") (pintype "passive"))
      (node (ref "R17") (pin "2") (pinfunction "2_2") (pintype "passive"))
      (node (ref "R19") (pin "1") (pinfunction "1_1") (pintype "passive"))
    )
    (net (code "36") (name "Net-(IC1-3V3OUT)") (class "Default")
      (node (ref "C7") (pin "1") (pinfunction "1_1") (pintype "passive"))
      (node (ref "IC1") (pin "17") (pinfunction "3V3OUT_17") (pintype "output"))
    )
    (net (code "37") (name "Net-(IC1-~{RESET})") (class "Default")
      (node (ref "IC1") (pin "19") (pinfunction "~{RESET}_19") (pintype "input"))
      (node (ref "R18") (pin "2") (pinfunction "2_2") (pintype "passive"))
    )
    (net (code "38") (name "Net-(IC8-AVCC)") (class "Default")
      (node (ref "C16") (pin "1") (pinfunction "1_1") (pintype "passive"))
      (node (ref "IC8") (pin "39") (pinfunction "AVCC_39") (pintype "power_in"))
      (node (ref "L3") (pin "1") (pinfunction "1_1") (pintype "passive"))
    )
    (net (code "39") (name "Net-(IC8-OC0B{slash}XCK0{slash}PD1)") (class "Default")
      (node (ref "IC8") (pin "21") (pinfunction "OC0B/XCK0/PD1_21") (pintype "bidirectional"))
      (node (ref "TP9") (pin "TP") (pinfunction "TP_TP") (pintype "input"))
    )
    (net (code "40") (name "Net-(IC8-PA4{slash}ADC4)") (class "Default")
      (node (ref "IC8") (pin "44") (pinfunction "PA4/ADC4_44") (pintype "bidirectional"))
      (node (ref "TP4") (pin "TP") (pinfunction "TP_TP") (pintype "input"))
    )
    (net (code "41") (name "Net-(IC8-PA5{slash}ADC5)") (class "Default")
      (node (ref "IC8") (pin "1") (pinfunction "PA5/ADC5_1") (pintype "bidirectional"))
      (node (ref "TP5") (pin "TP") (pinfunction "TP_TP") (pintype "input"))
    )
    (net (code "42") (name "Net-(IC8-PB2{slash}ADC10{slash}DAC0)") (class "Default")
      (node (ref "IC8") (pin "6") (pinfunction "PB2/ADC10/DAC0_6") (pintype "bidirectional"))
      (node (ref "TP6") (pin "TP") (pinfunction "TP_TP") (pintype "input"))
    )
    (net (code "43") (name "Net-(IC8-PC1{slash}OC0B{slash}XCK0{slash}SCL)") (class "Default")
      (node (ref "IC8") (pin "11") (pinfunction "PC1/OC0B/XCK0/SCL_11") (pintype "bidirectional"))
      (node (ref "TP8") (pin "TP") (pinfunction "TP_TP") (pintype "input"))
    )
    (net (code "44") (name "Net-(IC8-PR1{slash}XTAL1)") (class "Default")
      (node (ref "IC8") (pin "37") (pinfunction "PR1/XTAL1_37") (pintype "bidirectional"))
      (node (ref "OSC1") (pin "P$3") (pinfunction "OUTPUT_P$3") (pintype "passive"))
    )
    (net (code "45") (name "Net-(IC9-OUT)") (class "Default")
      (node (ref "C24") (pin "1") (pinfunction "1_1") (pintype "passive"))
      (node (ref "IC9") (pin "5") (pinfunction "OUT_5") (pintype "bidirectional"))
      (node (ref "R5") (pin "1") (pinfunction "1_1") (pintype "passive"))
    )
    (net (code "46") (name "Net-(IC10-+IN)") (class "Default")
      (node (ref "IC10") (pin "3") (pinfunction "+IN_3") (pintype "input"))
      (node (ref "R20") (pin "1") (pinfunction "1_1") (pintype "passive"))
      (node (ref "R21") (pin "2") (pinfunction "2_2") (pintype "passive"))
    )
    (net (code "47") (name "Net-(IC10--IN)") (class "Default")
      (node (ref "IC10") (pin "1") (pinfunction "OUT_1") (pintype "output"))
      (node (ref "IC10") (pin "4") (pinfunction "-IN_4") (pintype "input"))
      (node (ref "R17") (pin "1") (pinfunction "1_1") (pintype "passive"))
    )
    (net (code "48") (name "Net-(R1-Pad2)") (class "Default")
      (node (ref "R1") (pin "2") (pinfunction "2_2") (pintype "passive"))
      (node (ref "STATE") (pin "C") (pinfunction "C_C") (pintype "passive"))
    )
    (net (code "49") (name "Net-(R2-Pad2)") (class "Default")
      (node (ref "R2") (pin "2") (pinfunction "2_2") (pintype "passive"))
      (node (ref "R5") (pin "2") (pinfunction "2_2") (pintype "passive"))
      (node (ref "X8") (pin "1") (pinfunction "1_1") (pintype "passive"))
    )
    (net (code "50") (name "Net-(X4B-S)") (class "Default")
      (node (ref "R10") (pin "1") (pinfunction "1_1") (pintype "passive"))
      (node (ref "R11") (pin "1") (pinfunction "1_1") (pintype "passive"))
      (node (ref "X4") (pin "2") (pinfunction "S_2") (pintype "passive"))
    )
    (net (code "51") (name "Net-(X6-2)") (class "Default")
      (node (ref "IC7") (pin "P$4") (pinfunction "IO2_P$4") (pintype "bidirectional"))
      (node (ref "X6") (pin "P$2") (pinfunction "2_P$2") (pintype "bidirectional"))
    )
    (net (code "52") (name "Net-(X6-3)") (class "Default")
      (node (ref "IC7") (pin "P$6") (pinfunction "IO1_P$6") (pintype "bidirectional"))
      (node (ref "X6") (pin "P$3") (pinfunction "3_P$3") (pintype "bidirectional"))
    )
    (net (code "53") (name "Net-(X6-P$3)") (class "Default")
      (node (ref "C2") (pin "1") (pinfunction "1_1") (pintype "passive"))
      (node (ref "X6") (pin "SHIELD_3") (pinfunction "P$3_SHIELD_3") (pintype "bidirectional"))
    )
    (net (code "54") (name "Net-(X6-P$4)") (class "Default")
      (node (ref "R3") (pin "2") (pinfunction "2_2") (pintype "passive"))
      (node (ref "X6") (pin "SHIELD_4") (pinfunction "P$4_SHIELD_4") (pintype "bidirectional"))
    )
    (net (code "55") (name "VDD") (class "Default")
      (node (ref "X1") (pin "1") (pinfunction "1_1") (pintype "passive"))
      (node (ref "X7") (pin "P1") (pinfunction "1_P1") (pintype "passive"))
    )
    (net (code "56") (name "unconnected-(IC1-CBUS0-Pad23)") (class "Default")
      (node (ref "IC1") (pin "23") (pinfunction "CBUS0_23") (pintype "bidirectional"))
    )
    (net (code "57") (name "unconnected-(IC1-CBUS1-Pad22)") (class "Default")
      (node (ref "IC1") (pin "22") (pinfunction "CBUS1_22") (pintype "bidirectional"))
    )
    (net (code "58") (name "unconnected-(IC1-CBUS2-Pad13)") (class "Default")
      (node (ref "IC1") (pin "13") (pinfunction "CBUS2_13") (pintype "bidirectional"))
    )
    (net (code "59") (name "unconnected-(IC1-CBUS3-Pad14)") (class "Default")
      (node (ref "IC1") (pin "14") (pinfunction "CBUS3_14") (pintype "bidirectional"))
    )
    (net (code "60") (name "unconnected-(IC1-CBUS4-Pad12)") (class "Default")
      (node (ref "IC1") (pin "12") (pinfunction "CBUS4_12") (pintype "bidirectional"))
    )
    (net (code "61") (name "unconnected-(IC1-OSCI-Pad27)") (class "Default")
      (node (ref "IC1") (pin "27") (pinfunction "OSCI_27") (pintype "input"))
    )
    (net (code "62") (name "unconnected-(IC1-OSCO-Pad28)") (class "Default")
      (node (ref "IC1") (pin "28") (pinfunction "OSCO_28") (pintype "output"))
    )
    (net (code "63") (name "unconnected-(IC1-~{DCD}-Pad10)") (class "Default")
      (node (ref "IC1") (pin "10") (pinfunction "~{DCD}_10") (pintype "input"))
    )
    (net (code "64") (name "unconnected-(IC1-~{DSR}-Pad9)") (class "Default")
      (node (ref "IC1") (pin "9") (pinfunction "~{DSR}_9") (pintype "input"))
    )
    (net (code "65") (name "unconnected-(IC1-~{DTR}-Pad2)") (class "Default")
      (node (ref "IC1") (pin "2") (pinfunction "~{DTR}_2") (pintype "output"))
    )
    (net (code "66") (name "unconnected-(IC1-~{RI}-Pad6)") (class "Default")
      (node (ref "IC1") (pin "6") (pinfunction "~{RI}_6") (pintype "input"))
    )
    (net (code "67") (name "unconnected-(IC3-N{slash}C-Pad4)") (class "Default")
      (node (ref "IC3") (pin "4") (pinfunction "N/C_4") (pintype "bidirectional"))
    )
    (net (code "68") (name "unconnected-(IC8-D+{slash}TXD1{slash}SCK{slash}PD7-Pad27)") (class "Default")
      (node (ref "IC8") (pin "27") (pinfunction "D+/TXD1/SCK/PD7_27") (pintype "bidirectional"))
    )
    (net (code "69") (name "unconnected-(IC8-D-{slash}RXD1{slash}MISO{slash}PD6-Pad26)") (class "Default")
      (node (ref "IC8") (pin "26") (pinfunction "D-/RXD1/MISO/PD6_26") (pintype "bidirectional"))
    )
    (net (code "70") (name "unconnected-(IC8-OC0A{slash}PD0-Pad20)") (class "Default")
      (node (ref "IC8") (pin "20") (pinfunction "OC0A/PD0_20") (pintype "bidirectional"))
    )
    (net (code "71") (name "unconnected-(IC8-OC1A{slash}~{SS}{slash}PD4-Pad24)") (class "Default")
      (node (ref "IC8") (pin "24") (pinfunction "OC1A/~{SS}/PD4_24") (pintype "bidirectional"))
    )
    (net (code "72") (name "unconnected-(IC8-OCB1{slash}XCK1{slash}MOSI{slash}PD5-Pad25)") (class "Default")
      (node (ref "IC8") (pin "25") (pinfunction "OCB1/XCK1/MOSI/PD5_25") (pintype "bidirectional"))
    )
    (net (code "73") (name "unconnected-(IC8-PA3{slash}ADC3-Pad43)") (class "Default")
      (node (ref "IC8") (pin "43") (pinfunction "PA3/ADC3_43") (pintype "bidirectional"))
    )
    (net (code "74") (name "unconnected-(IC8-PA6{slash}ADC6{slash}AC1-OUT-Pad2)") (class "Default")
      (node (ref "IC8") (pin "2") (pinfunction "PA6/ADC6/AC1-OUT_2") (pintype "bidirectional"))
    )
    (net (code "75") (name "unconnected-(IC8-PA7{slash}ADC7{slash}AC0-OUT-Pad3)") (class "Default")
      (node (ref "IC8") (pin "3") (pinfunction "PA7/ADC7/AC0-OUT_3") (pintype "bidirectional"))
    )
    (net (code "76") (name "unconnected-(IC8-PB1{slash}ADC9-Pad5)") (class "Default")
      (node (ref "IC8") (pin "5") (pinfunction "PB1/ADC9_5") (pintype "bidirectional"))
    )
    (net (code "77") (name "unconnected-(IC8-PB3{slash}ADC11{slash}DAC1-Pad7)") (class "Default")
      (node (ref "IC8") (pin "7") (pinfunction "PB3/ADC11/DAC1_7") (pintype "bidirectional"))
    )
    (net (code "78") (name "unconnected-(IC8-PC7{slash}SCK{slash}TXD1{slash}CLKO{slash}EVO-Pad17)") (class "Default")
      (node (ref "IC8") (pin "17") (pinfunction "PC7/SCK/TXD1/CLKO/EVO_17") (pintype "bidirectional"))
    )
    (net (code "79") (name "unconnected-(IC9-N{slash}C-Pad4)") (class "Default")
      (node (ref "IC9") (pin "4") (pinfunction "N/C_4") (pintype "bidirectional"))
    )
    (net (code "80") (name "unconnected-(OSC1-STANDBY#-PadP$1)") (class "Default")
      (node (ref "OSC1") (pin "P$1") (pinfunction "STANDBY#_P$1") (pintype "passive"))
    )
    (net (code "81") (name "unconnected-(SV2-Pad3)") (class "Default")
      (node (ref "SV2") (pin "3") (pinfunction "3_3") (pintype "passive"))
    )
    (net (code "82") (name "unconnected-(SV2-Pad4)") (class "Default")
      (node (ref "SV2") (pin "4") (pinfunction "4_4") (pintype "passive"))
    )
    (net (code "83") (name "unconnected-(X2D-S-Pad4)") (class "Default")
      (node (ref "X2") (pin "4") (pinfunction "S_4") (pintype "passive"))
    )
    (net (code "84") (name "unconnected-(X6-4-PadP$4)") (class "Default")
      (node (ref "X6") (pin "P$4") (pinfunction "4_P$4") (pintype "bidirectional"))
    )
    (net (code "85") (name "unconnected-(X6-P$1-PadSHIELD_1)") (class "Default")
      (node (ref "X6") (pin "SHIELD_1") (pinfunction "P$1_SHIELD_1") (pintype "bidirectional"))
    )
    (net (code "86") (name "unconnected-(X6-P$2-PadSHIELD_2)") (class "Default")
      (node (ref "X6") (pin "SHIELD_2") (pinfunction "P$2_SHIELD_2") (pintype "bidirectional"))
    )
  )
)
